# G1000_Buttons_Left.net
KiCad netlist of a schematic drawn in EasyEDA
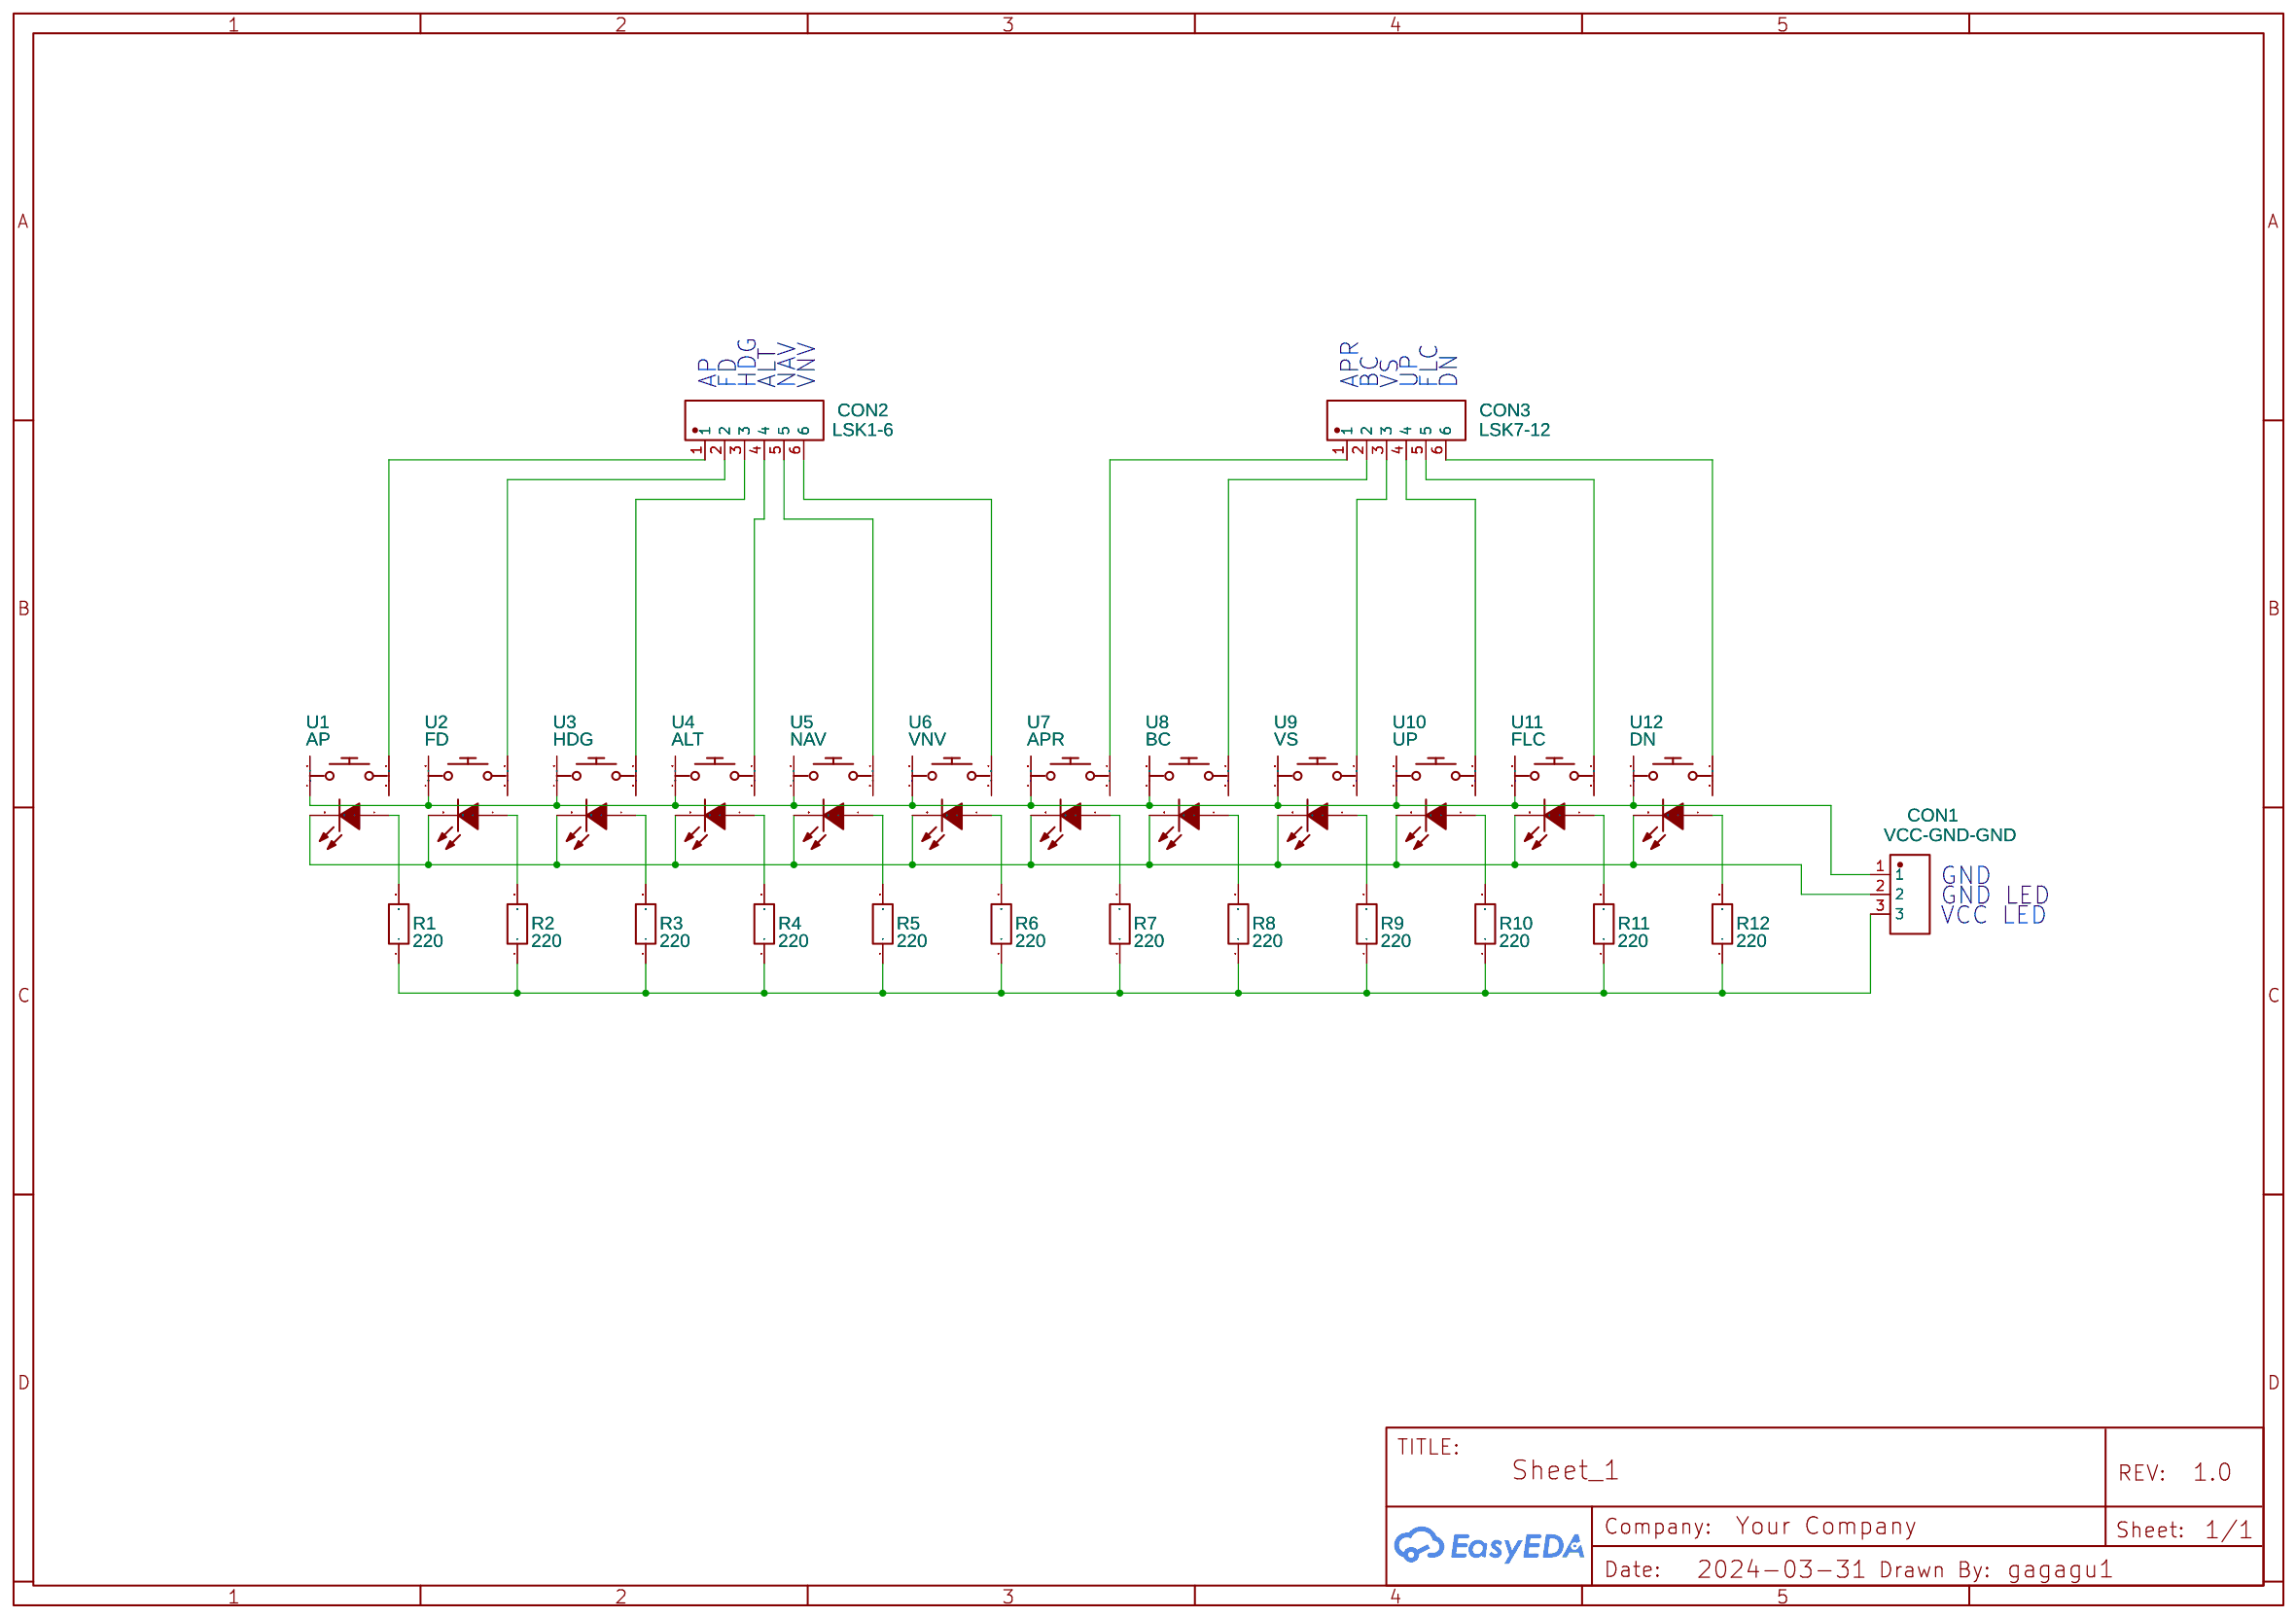
[diagram p0: schematic sheet]

(export (version "E")
  (design (tool "Eeschema 10.0.6"))
  (components
    (comp (ref "CON1")
      (value "VCC-GND-GND")
      (fields (field (name "Manufacturer Part") "HC-XH-3A-G") (field (name "Manufacturer") "HCTL(华灿天禄)"))
      (libsource (lib "") (part "HC-XH-3A-G"))
    )
    (comp (ref "CON2")
      (value "LSK1-6")
      (fields (field (name "Manufacturer Part") "XH-6A") (field (name "Manufacturer") "CAX"))
      (libsource (lib "") (part "ARUN-CONN-TH_XH-6A"))
    )
    (comp (ref "CON3")
      (value "LSK7-12")
      (fields (field (name "Manufacturer Part") "XH-6A") (field (name "Manufacturer") "CAX"))
      (libsource (lib "") (part "ARUN-CONN-TH_XH-6A"))
    )
    (comp (ref "R1") (value "220") (libsource (lib "") (part "R_AXIAL-0.4_EU")))
    (comp (ref "R2") (value "220") (libsource (lib "") (part "R_AXIAL-0.4_EU")))
    (comp (ref "R3") (value "220") (libsource (lib "") (part "R_AXIAL-0.4_EU")))
    (comp (ref "R4") (value "220") (libsource (lib "") (part "R_AXIAL-0.4_EU")))
    (comp (ref "R5") (value "220") (libsource (lib "") (part "R_AXIAL-0.4_EU")))
    (comp (ref "R6") (value "220") (libsource (lib "") (part "R_AXIAL-0.4_EU")))
    (comp (ref "R7") (value "220") (libsource (lib "") (part "R_AXIAL-0.4_EU")))
    (comp (ref "R8") (value "220") (libsource (lib "") (part "R_AXIAL-0.4_EU")))
    (comp (ref "R9") (value "220") (libsource (lib "") (part "R_AXIAL-0.4_EU")))
    (comp (ref "R10") (value "220") (libsource (lib "") (part "R_AXIAL-0.4_EU")))
    (comp (ref "R11") (value "220") (libsource (lib "") (part "R_AXIAL-0.4_EU")))
    (comp (ref "R12") (value "220") (libsource (lib "") (part "R_AXIAL-0.4_EU")))
    (comp (ref "U1") (value "AP") (libsource (lib "") (part "6X6_LED+PUSHBUTTON V2")))
    (comp (ref "U2") (value "FD") (libsource (lib "") (part "6X6_LED+PUSHBUTTON V2")))
    (comp (ref "U3") (value "HDG") (libsource (lib "") (part "6X6_LED+PUSHBUTTON V2")))
    (comp (ref "U4") (value "ALT") (libsource (lib "") (part "6X6_LED+PUSHBUTTON V2")))
    (comp (ref "U5") (value "NAV") (libsource (lib "") (part "6X6_LED+PUSHBUTTON V2")))
    (comp (ref "U6") (value "VNV") (libsource (lib "") (part "6X6_LED+PUSHBUTTON V2")))
    (comp (ref "U7") (value "APR") (libsource (lib "") (part "6X6_LED+PUSHBUTTON V2")))
    (comp (ref "U8") (value "BC") (libsource (lib "") (part "6X6_LED+PUSHBUTTON V2")))
    (comp (ref "U9") (value "VS") (libsource (lib "") (part "6X6_LED+PUSHBUTTON V2")))
    (comp (ref "U10") (value "UP") (libsource (lib "") (part "6X6_LED+PUSHBUTTON V2")))
    (comp (ref "U11") (value "FLC") (libsource (lib "") (part "6X6_LED+PUSHBUTTON V2")))
    (comp (ref "U12") (value "DN") (libsource (lib "") (part "6X6_LED+PUSHBUTTON V2")))
  )
  (nets
    (net (code "1") (name "Net-(CON1-Pad1)") (class "Default")
      (node (ref "CON1") (pin "1") (pinfunction "1_1") (pintype "unspecified"))
      (node (ref "U1") (pin "4") (pinfunction "4_4") (pintype "unspecified"))
      (node (ref "U10") (pin "4") (pinfunction "4_4") (pintype "unspecified"))
      (node (ref "U11") (pin "4") (pinfunction "4_4") (pintype "unspecified"))
      (node (ref "U12") (pin "4") (pinfunction "4_4") (pintype "unspecified"))
      (node (ref "U2") (pin "4") (pinfunction "4_4") (pintype "unspecified"))
      (node (ref "U3") (pin "4") (pinfunction "4_4") (pintype "unspecified"))
      (node (ref "U4") (pin "4") (pinfunction "4_4") (pintype "unspecified"))
      (node (ref "U5") (pin "4") (pinfunction "4_4") (pintype "unspecified"))
      (node (ref "U6") (pin "4") (pinfunction "4_4") (pintype "unspecified"))
      (node (ref "U7") (pin "4") (pinfunction "4_4") (pintype "unspecified"))
      (node (ref "U8") (pin "4") (pinfunction "4_4") (pintype "unspecified"))
      (node (ref "U9") (pin "4") (pinfunction "4_4") (pintype "unspecified"))
    )
    (net (code "2") (name "Net-(CON1-Pad2)") (class "Default")
      (node (ref "CON1") (pin "2") (pinfunction "2_2") (pintype "unspecified"))
      (node (ref "U1") (pin "C") (pinfunction "C_C") (pintype "unspecified"))
      (node (ref "U10") (pin "C") (pinfunction "C_C") (pintype "unspecified"))
      (node (ref "U11") (pin "C") (pinfunction "C_C") (pintype "unspecified"))
      (node (ref "U12") (pin "C") (pinfunction "C_C") (pintype "unspecified"))
      (node (ref "U2") (pin "C") (pinfunction "C_C") (pintype "unspecified"))
      (node (ref "U3") (pin "C") (pinfunction "C_C") (pintype "unspecified"))
      (node (ref "U4") (pin "C") (pinfunction "C_C") (pintype "unspecified"))
      (node (ref "U5") (pin "C") (pinfunction "C_C") (pintype "unspecified"))
      (node (ref "U6") (pin "C") (pinfunction "C_C") (pintype "unspecified"))
      (node (ref "U7") (pin "C") (pinfunction "C_C") (pintype "unspecified"))
      (node (ref "U8") (pin "C") (pinfunction "C_C") (pintype "unspecified"))
      (node (ref "U9") (pin "C") (pinfunction "C_C") (pintype "unspecified"))
    )
    (net (code "3") (name "Net-(CON1-Pad3)") (class "Default")
      (node (ref "CON1") (pin "3") (pinfunction "3_3") (pintype "unspecified"))
      (node (ref "R1") (pin "1") (pinfunction "1_1") (pintype "unspecified"))
      (node (ref "R10") (pin "1") (pinfunction "1_1") (pintype "unspecified"))
      (node (ref "R11") (pin "1") (pinfunction "1_1") (pintype "unspecified"))
      (node (ref "R12") (pin "1") (pinfunction "1_1") (pintype "unspecified"))
      (node (ref "R2") (pin "1") (pinfunction "1_1") (pintype "unspecified"))
      (node (ref "R3") (pin "1") (pinfunction "1_1") (pintype "unspecified"))
      (node (ref "R4") (pin "1") (pinfunction "1_1") (pintype "unspecified"))
      (node (ref "R5") (pin "1") (pinfunction "1_1") (pintype "unspecified"))
      (node (ref "R6") (pin "1") (pinfunction "1_1") (pintype "unspecified"))
      (node (ref "R7") (pin "1") (pinfunction "1_1") (pintype "unspecified"))
      (node (ref "R8") (pin "1") (pinfunction "1_1") (pintype "unspecified"))
      (node (ref "R9") (pin "1") (pinfunction "1_1") (pintype "unspecified"))
    )
    (net (code "4") (name "Net-(CON2-Pad1)") (class "Default")
      (node (ref "CON2") (pin "1") (pinfunction "1_1") (pintype "unspecified"))
      (node (ref "U1") (pin "1") (pinfunction "1_1") (pintype "unspecified"))
    )
    (net (code "5") (name "Net-(CON2-Pad2)") (class "Default")
      (node (ref "CON2") (pin "2") (pinfunction "2_2") (pintype "unspecified"))
      (node (ref "U2") (pin "1") (pinfunction "1_1") (pintype "unspecified"))
    )
    (net (code "6") (name "Net-(CON2-Pad3)") (class "Default")
      (node (ref "CON2") (pin "3") (pinfunction "3_3") (pintype "unspecified"))
      (node (ref "U3") (pin "1") (pinfunction "1_1") (pintype "unspecified"))
    )
    (net (code "7") (name "Net-(CON2-Pad4)") (class "Default")
      (node (ref "CON2") (pin "4") (pinfunction "4_4") (pintype "unspecified"))
      (node (ref "U4") (pin "1") (pinfunction "1_1") (pintype "unspecified"))
    )
    (net (code "8") (name "Net-(CON2-Pad5)") (class "Default")
      (node (ref "CON2") (pin "5") (pinfunction "5_5") (pintype "unspecified"))
      (node (ref "U5") (pin "1") (pinfunction "1_1") (pintype "unspecified"))
    )
    (net (code "9") (name "Net-(CON2-Pad6)") (class "Default")
      (node (ref "CON2") (pin "6") (pinfunction "6_6") (pintype "unspecified"))
      (node (ref "U6") (pin "1") (pinfunction "1_1") (pintype "unspecified"))
    )
    (net (code "10") (name "Net-(CON3-Pad1)") (class "Default")
      (node (ref "CON3") (pin "1") (pinfunction "1_1") (pintype "unspecified"))
      (node (ref "U7") (pin "1") (pinfunction "1_1") (pintype "unspecified"))
    )
    (net (code "11") (name "Net-(CON3-Pad2)") (class "Default")
      (node (ref "CON3") (pin "2") (pinfunction "2_2") (pintype "unspecified"))
      (node (ref "U8") (pin "1") (pinfunction "1_1") (pintype "unspecified"))
    )
    (net (code "12") (name "Net-(CON3-Pad3)") (class "Default")
      (node (ref "CON3") (pin "3") (pinfunction "3_3") (pintype "unspecified"))
      (node (ref "U9") (pin "1") (pinfunction "1_1") (pintype "unspecified"))
    )
    (net (code "13") (name "Net-(CON3-Pad4)") (class "Default")
      (node (ref "CON3") (pin "4") (pinfunction "4_4") (pintype "unspecified"))
      (node (ref "U10") (pin "1") (pinfunction "1_1") (pintype "unspecified"))
    )
    (net (code "14") (name "Net-(CON3-Pad5)") (class "Default")
      (node (ref "CON3") (pin "5") (pinfunction "5_5") (pintype "unspecified"))
      (node (ref "U11") (pin "1") (pinfunction "1_1") (pintype "unspecified"))
    )
    (net (code "15") (name "Net-(CON3-Pad6)") (class "Default")
      (node (ref "CON3") (pin "6") (pinfunction "6_6") (pintype "unspecified"))
      (node (ref "U12") (pin "1") (pinfunction "1_1") (pintype "unspecified"))
    )
    (net (code "16") (name "Net-(R1-Pad2)") (class "Default")
      (node (ref "R1") (pin "2") (pinfunction "2_2") (pintype "unspecified"))
      (node (ref "U1") (pin "A") (pinfunction "A_A") (pintype "unspecified"))
    )
    (net (code "17") (name "Net-(R2-Pad2)") (class "Default")
      (node (ref "R2") (pin "2") (pinfunction "2_2") (pintype "unspecified"))
      (node (ref "U2") (pin "A") (pinfunction "A_A") (pintype "unspecified"))
    )
    (net (code "18") (name "Net-(R3-Pad2)") (class "Default")
      (node (ref "R3") (pin "2") (pinfunction "2_2") (pintype "unspecified"))
      (node (ref "U3") (pin "A") (pinfunction "A_A") (pintype "unspecified"))
    )
    (net (code "19") (name "Net-(R4-Pad2)") (class "Default")
      (node (ref "R4") (pin "2") (pinfunction "2_2") (pintype "unspecified"))
      (node (ref "U4") (pin "A") (pinfunction "A_A") (pintype "unspecified"))
    )
    (net (code "20") (name "Net-(R5-Pad2)") (class "Default")
      (node (ref "R5") (pin "2") (pinfunction "2_2") (pintype "unspecified"))
      (node (ref "U5") (pin "A") (pinfunction "A_A") (pintype "unspecified"))
    )
    (net (code "21") (name "Net-(R6-Pad2)") (class "Default")
      (node (ref "R6") (pin "2") (pinfunction "2_2") (pintype "unspecified"))
      (node (ref "U6") (pin "A") (pinfunction "A_A") (pintype "unspecified"))
    )
    (net (code "22") (name "Net-(R7-Pad2)") (class "Default")
      (node (ref "R7") (pin "2") (pinfunction "2_2") (pintype "unspecified"))
      (node (ref "U7") (pin "A") (pinfunction "A_A") (pintype "unspecified"))
    )
    (net (code "23") (name "Net-(R8-Pad2)") (class "Default")
      (node (ref "R8") (pin "2") (pinfunction "2_2") (pintype "unspecified"))
      (node (ref "U8") (pin "A") (pinfunction "A_A") (pintype "unspecified"))
    )
    (net (code "24") (name "Net-(R9-Pad2)") (class "Default")
      (node (ref "R9") (pin "2") (pinfunction "2_2") (pintype "unspecified"))
      (node (ref "U9") (pin "A") (pinfunction "A_A") (pintype "unspecified"))
    )
    (net (code "25") (name "Net-(R10-Pad2)") (class "Default")
      (node (ref "R10") (pin "2") (pinfunction "2_2") (pintype "unspecified"))
      (node (ref "U10") (pin "A") (pinfunction "A_A") (pintype "unspecified"))
    )
    (net (code "26") (name "Net-(R11-Pad2)") (class "Default")
      (node (ref "R11") (pin "2") (pinfunction "2_2") (pintype "unspecified"))
      (node (ref "U11") (pin "A") (pinfunction "A_A") (pintype "unspecified"))
    )
    (net (code "27") (name "Net-(R12-Pad2)") (class "Default")
      (node (ref "R12") (pin "2") (pinfunction "2_2") (pintype "unspecified"))
      (node (ref "U12") (pin "A") (pinfunction "A_A") (pintype "unspecified"))
    )
    (net (code "28") (name "unconnected-(U1-Pad2)") (class "Default")
      (node (ref "U1") (pin "2") (pinfunction "2_2") (pintype "unspecified"))
    )
    (net (code "29") (name "unconnected-(U1-Pad3)") (class "Default")
      (node (ref "U1") (pin "3") (pinfunction "3_3") (pintype "unspecified"))
    )
    (net (code "30") (name "unconnected-(U2-Pad2)") (class "Default")
      (node (ref "U2") (pin "2") (pinfunction "2_2") (pintype "unspecified"))
    )
    (net (code "31") (name "unconnected-(U2-Pad3)") (class "Default")
      (node (ref "U2") (pin "3") (pinfunction "3_3") (pintype "unspecified"))
    )
    (net (code "32") (name "unconnected-(U3-Pad2)") (class "Default")
      (node (ref "U3") (pin "2") (pinfunction "2_2") (pintype "unspecified"))
    )
    (net (code "33") (name "unconnected-(U3-Pad3)") (class "Default")
      (node (ref "U3") (pin "3") (pinfunction "3_3") (pintype "unspecified"))
    )
    (net (code "34") (name "unconnected-(U4-Pad2)") (class "Default")
      (node (ref "U4") (pin "2") (pinfunction "2_2") (pintype "unspecified"))
    )
    (net (code "35") (name "unconnected-(U4-Pad3)") (class "Default")
      (node (ref "U4") (pin "3") (pinfunction "3_3") (pintype "unspecified"))
    )
    (net (code "36") (name "unconnected-(U5-Pad2)") (class "Default")
      (node (ref "U5") (pin "2") (pinfunction "2_2") (pintype "unspecified"))
    )
    (net (code "37") (name "unconnected-(U5-Pad3)") (class "Default")
      (node (ref "U5") (pin "3") (pinfunction "3_3") (pintype "unspecified"))
    )
    (net (code "38") (name "unconnected-(U6-Pad2)") (class "Default")
      (node (ref "U6") (pin "2") (pinfunction "2_2") (pintype "unspecified"))
    )
    (net (code "39") (name "unconnected-(U6-Pad3)") (class "Default")
      (node (ref "U6") (pin "3") (pinfunction "3_3") (pintype "unspecified"))
    )
    (net (code "40") (name "unconnected-(U7-Pad2)") (class "Default")
      (node (ref "U7") (pin "2") (pinfunction "2_2") (pintype "unspecified"))
    )
    (net (code "41") (name "unconnected-(U7-Pad3)") (class "Default")
      (node (ref "U7") (pin "3") (pinfunction "3_3") (pintype "unspecified"))
    )
    (net (code "42") (name "unconnected-(U8-Pad2)") (class "Default")
      (node (ref "U8") (pin "2") (pinfunction "2_2") (pintype "unspecified"))
    )
    (net (code "43") (name "unconnected-(U8-Pad3)") (class "Default")
      (node (ref "U8") (pin "3") (pinfunction "3_3") (pintype "unspecified"))
    )
    (net (code "44") (name "unconnected-(U9-Pad2)") (class "Default")
      (node (ref "U9") (pin "2") (pinfunction "2_2") (pintype "unspecified"))
    )
    (net (code "45") (name "unconnected-(U9-Pad3)") (class "Default")
      (node (ref "U9") (pin "3") (pinfunction "3_3") (pintype "unspecified"))
    )
    (net (code "46") (name "unconnected-(U10-Pad2)") (class "Default")
      (node (ref "U10") (pin "2") (pinfunction "2_2") (pintype "unspecified"))
    )
    (net (code "47") (name "unconnected-(U10-Pad3)") (class "Default")
      (node (ref "U10") (pin "3") (pinfunction "3_3") (pintype "unspecified"))
    )
    (net (code "48") (name "unconnected-(U11-Pad2)") (class "Default")
      (node (ref "U11") (pin "2") (pinfunction "2_2") (pintype "unspecified"))
    )
    (net (code "49") (name "unconnected-(U11-Pad3)") (class "Default")
      (node (ref "U11") (pin "3") (pinfunction "3_3") (pintype "unspecified"))
    )
    (net (code "50") (name "unconnected-(U12-Pad2)") (class "Default")
      (node (ref "U12") (pin "2") (pinfunction "2_2") (pintype "unspecified"))
    )
    (net (code "51") (name "unconnected-(U12-Pad3)") (class "Default")
      (node (ref "U12") (pin "3") (pinfunction "3_3") (pintype "unspecified"))
    )
  )
)
